# Z80UARTTEST.net
KiCad netlist of a schematic drawn in EAGLE
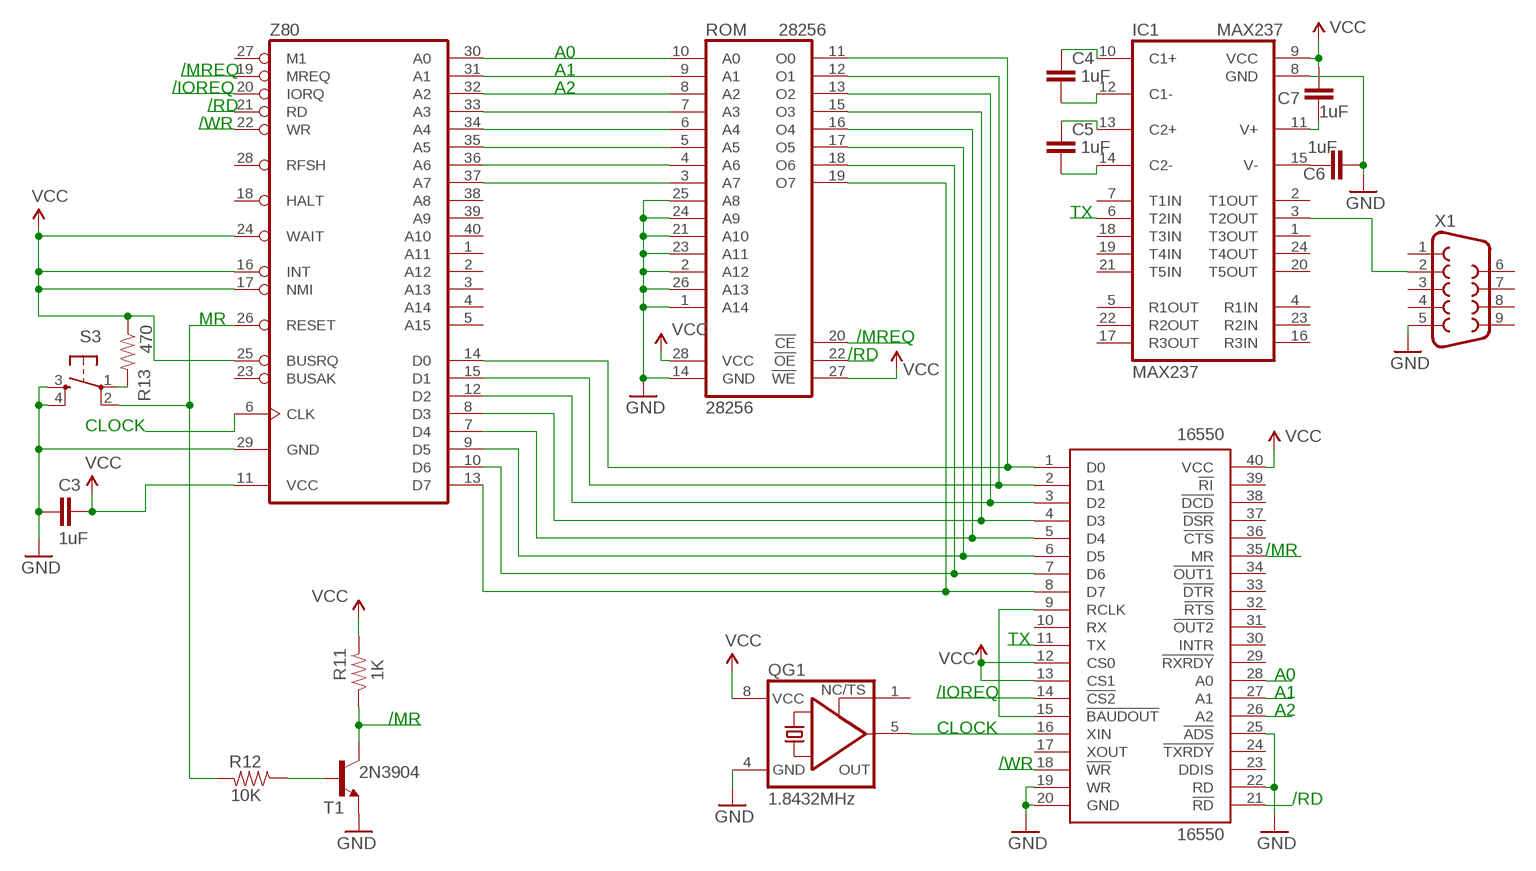
[diagram p0: schematic, sheet 1]

(export (version "E")
  (design (tool "Eeschema 10.0.6"))
  (components
    (comp (ref "C3")
      (value "1uF")
      (footprint "eagle-import:E5-5")
      (libsource (lib "eagle-import") (part "CAP"))
    )
    (comp (ref "C4")
      (value "1uF")
      (footprint "eagle-import:E5-5")
      (libsource (lib "eagle-import") (part "CAP"))
    )
    (comp (ref "C5")
      (value "1uF")
      (footprint "eagle-import:E5-5")
      (libsource (lib "eagle-import") (part "CAP"))
    )
    (comp (ref "C6")
      (value "1uF")
      (footprint "eagle-import:E5-5")
      (libsource (lib "eagle-import") (part "CAP"))
    )
    (comp (ref "C7")
      (value "1uF")
      (footprint "eagle-import:E5-5")
      (libsource (lib "eagle-import") (part "CAP"))
    )
    (comp (ref "IC1")
      (value "MAX237")
      (footprint "eagle-import:DIL24-3")
      (fields (field (name "MPN") "MAX237CNG+"))
      (libsource (lib "eagle-import") (part "MAX237"))
    )
    (comp (ref "QG1")
      (value "1.8432MHz")
      (footprint "eagle-import:DIL08S")
      (libsource (lib "eagle-import") (part "XO-8"))
    )
    (comp (ref "R11")
      (value "1K")
      (footprint "eagle-import:AXIAL-0.4")
      (libsource (lib "eagle-import") (part "RESISTORPTH-1/4W"))
    )
    (comp (ref "R12")
      (value "10K")
      (footprint "eagle-import:AXIAL-0.4")
      (libsource (lib "eagle-import") (part "RESISTORPTH-1/4W"))
    )
    (comp (ref "R13")
      (value "470")
      (footprint "eagle-import:AXIAL-0.4")
      (libsource (lib "eagle-import") (part "RESISTORPTH-1/4W"))
    )
    (comp (ref "ROM")
      (value "28256")
      (footprint "eagle-import:DIL28")
      (libsource (lib "eagle-import") (part "28256"))
    )
    (comp (ref "S3")
      (value "TAC_SWITCHPTH")
      (footprint "eagle-import:TACTILE-PTH")
      (libsource (lib "eagle-import") (part "TAC_SWITCHPTH"))
    )
    (comp (ref "T1")
      (value "2N3904")
      (footprint "eagle-import:TO92")
      (libsource (lib "eagle-import") (part "2N3904"))
    )
    (comp (ref "U$1")
      (value "16550")
      (footprint "eagle-import:DIL40")
      (libsource (lib "eagle-import") (part "16550"))
    )
    (comp (ref "X1")
      (value "DB9FEMALE")
      (footprint "eagle-import:DB9")
      (libsource (lib "eagle-import") (part "DB9FEMALE"))
    )
    (comp (ref "Z80")
      (value "Z80CPU")
      (footprint "eagle-import:DIL40")
      (libsource (lib "eagle-import") (part "Z80CPU"))
    )
  )
  (nets
    (net (code "1") (name "/A0") (class "Default")
      (node (ref "ROM") (pin "10") (pinfunction "A0_10") (pintype "input"))
      (node (ref "U$1") (pin "28") (pinfunction "A0_28") (pintype "bidirectional"))
      (node (ref "Z80") (pin "30") (pinfunction "A0_30") (pintype "output"))
    )
    (net (code "2") (name "/A1") (class "Default")
      (node (ref "ROM") (pin "9") (pinfunction "A1_9") (pintype "input"))
      (node (ref "U$1") (pin "27") (pinfunction "A1_27") (pintype "bidirectional"))
      (node (ref "Z80") (pin "31") (pinfunction "A1_31") (pintype "output"))
    )
    (net (code "3") (name "/A2") (class "Default")
      (node (ref "ROM") (pin "8") (pinfunction "A2_8") (pintype "input"))
      (node (ref "U$1") (pin "26") (pinfunction "A2_26") (pintype "bidirectional"))
      (node (ref "Z80") (pin "32") (pinfunction "A2_32") (pintype "output"))
    )
    (net (code "4") (name "/CLOCK") (class "Default")
      (node (ref "QG1") (pin "5") (pinfunction "OUT_5") (pintype "output"))
      (node (ref "U$1") (pin "16") (pinfunction "XIN_16") (pintype "bidirectional"))
      (node (ref "Z80") (pin "6") (pinfunction "CLK_6") (pintype "input"))
    )
    (net (code "5") (name "/TX") (class "Default")
      (node (ref "IC1") (pin "6") (pinfunction "T2IN_6") (pintype "input"))
      (node (ref "U$1") (pin "11") (pinfunction "TX_11") (pintype "bidirectional"))
    )
    (net (code "6") (name "/{slash}IOREQ") (class "Default")
      (node (ref "U$1") (pin "14") (pinfunction "~{CS2}_14") (pintype "bidirectional"))
      (node (ref "Z80") (pin "20") (pinfunction "IORQ_20") (pintype "output"))
    )
    (net (code "7") (name "/{slash}MR") (class "Default")
      (node (ref "R11") (pin "P$1") (pinfunction "1_P$1") (pintype "passive"))
      (node (ref "T1") (pin "1") (pinfunction "C_1") (pintype "passive"))
      (node (ref "U$1") (pin "35") (pinfunction "MR_35") (pintype "bidirectional"))
    )
    (net (code "8") (name "/{slash}MREQ") (class "Default")
      (node (ref "ROM") (pin "20") (pinfunction "~{CE}_20") (pintype "input"))
      (node (ref "Z80") (pin "19") (pinfunction "MREQ_19") (pintype "output"))
    )
    (net (code "9") (name "/{slash}RD") (class "Default")
      (node (ref "ROM") (pin "22") (pinfunction "~{OE}_22") (pintype "input"))
      (node (ref "U$1") (pin "21") (pinfunction "~{RD}_21") (pintype "bidirectional"))
      (node (ref "Z80") (pin "21") (pinfunction "RD_21") (pintype "output"))
    )
    (net (code "10") (name "/{slash}WR") (class "Default")
      (node (ref "U$1") (pin "18") (pinfunction "~{WR}_18") (pintype "bidirectional"))
      (node (ref "Z80") (pin "22") (pinfunction "WR_22") (pintype "output"))
    )
    (net (code "11") (name "GND") (class "Default")
      (node (ref "C3") (pin "-") (pinfunction "2_-") (pintype "passive"))
      (node (ref "C6") (pin "+") (pinfunction "1_+") (pintype "passive"))
      (node (ref "IC1") (pin "8") (pinfunction "GND_8") (pintype "bidirectional"))
      (node (ref "QG1") (pin "4") (pinfunction "GND_4") (pintype "power_in"))
      (node (ref "ROM") (pin "1") (pinfunction "A14_1") (pintype "input"))
      (node (ref "ROM") (pin "14") (pinfunction "GND_14") (pintype "tri_state"))
      (node (ref "ROM") (pin "2") (pinfunction "A12_2") (pintype "input"))
      (node (ref "ROM") (pin "21") (pinfunction "A10_21") (pintype "input"))
      (node (ref "ROM") (pin "23") (pinfunction "A11_23") (pintype "input"))
      (node (ref "ROM") (pin "24") (pinfunction "A9_24") (pintype "input"))
      (node (ref "ROM") (pin "25") (pinfunction "A8_25") (pintype "input"))
      (node (ref "ROM") (pin "26") (pinfunction "A13_26") (pintype "input"))
      (node (ref "S3") (pin "3") (pinfunction "3_3") (pintype "passive"))
      (node (ref "S3") (pin "4") (pinfunction "4_4") (pintype "passive"))
      (node (ref "T1") (pin "3") (pinfunction "E_3") (pintype "passive"))
      (node (ref "U$1") (pin "19") (pinfunction "WR_19") (pintype "bidirectional"))
      (node (ref "U$1") (pin "20") (pinfunction "GND_20") (pintype "bidirectional"))
      (node (ref "U$1") (pin "22") (pinfunction "RD_22") (pintype "bidirectional"))
      (node (ref "U$1") (pin "25") (pinfunction "~{ADS}_25") (pintype "bidirectional"))
      (node (ref "X1") (pin "5") (pinfunction "5_5") (pintype "passive"))
      (node (ref "Z80") (pin "29") (pinfunction "GND_29") (pintype "power_in"))
    )
    (net (code "12") (name "Net-(C4-1)") (class "Default")
      (node (ref "C4") (pin "+") (pinfunction "1_+") (pintype "passive"))
      (node (ref "IC1") (pin "10") (pinfunction "C1+_10") (pintype "bidirectional"))
    )
    (net (code "13") (name "Net-(C4-2)") (class "Default")
      (node (ref "C4") (pin "-") (pinfunction "2_-") (pintype "passive"))
      (node (ref "IC1") (pin "12") (pinfunction "C1-_12") (pintype "bidirectional"))
    )
    (net (code "14") (name "Net-(C5-1)") (class "Default")
      (node (ref "C5") (pin "+") (pinfunction "1_+") (pintype "passive"))
      (node (ref "IC1") (pin "13") (pinfunction "C2+_13") (pintype "bidirectional"))
    )
    (net (code "15") (name "Net-(C5-2)") (class "Default")
      (node (ref "C5") (pin "-") (pinfunction "2_-") (pintype "passive"))
      (node (ref "IC1") (pin "14") (pinfunction "C2-_14") (pintype "bidirectional"))
    )
    (net (code "16") (name "Net-(C6-2)") (class "Default")
      (node (ref "C6") (pin "-") (pinfunction "2_-") (pintype "passive"))
      (node (ref "IC1") (pin "15") (pinfunction "V-_15") (pintype "bidirectional"))
    )
    (net (code "17") (name "Net-(C7-1)") (class "Default")
      (node (ref "C7") (pin "+") (pinfunction "1_+") (pintype "passive"))
      (node (ref "IC1") (pin "11") (pinfunction "V+_11") (pintype "bidirectional"))
    )
    (net (code "18") (name "Net-(IC1-T2OUT)") (class "Default")
      (node (ref "IC1") (pin "3") (pinfunction "T2OUT_3") (pintype "output"))
      (node (ref "X1") (pin "2") (pinfunction "2_2") (pintype "passive"))
    )
    (net (code "19") (name "Net-(R12-1)") (class "Default")
      (node (ref "R12") (pin "P$1") (pinfunction "1_P$1") (pintype "passive"))
      (node (ref "T1") (pin "2") (pinfunction "B_2") (pintype "passive"))
    )
    (net (code "20") (name "Net-(R12-2)") (class "Default")
      (node (ref "R12") (pin "P$2") (pinfunction "2_P$2") (pintype "passive"))
      (node (ref "S3") (pin "2") (pinfunction "2_2") (pintype "passive"))
      (node (ref "Z80") (pin "26") (pinfunction "RESET_26") (pintype "input"))
    )
    (net (code "21") (name "Net-(R13-2)") (class "Default")
      (node (ref "R13") (pin "P$2") (pinfunction "2_P$2") (pintype "passive"))
      (node (ref "S3") (pin "1") (pinfunction "1_1") (pintype "passive"))
    )
    (net (code "22") (name "Net-(ROM-A3)") (class "Default")
      (node (ref "ROM") (pin "7") (pinfunction "A3_7") (pintype "input"))
      (node (ref "Z80") (pin "33") (pinfunction "A3_33") (pintype "output"))
    )
    (net (code "23") (name "Net-(ROM-A4)") (class "Default")
      (node (ref "ROM") (pin "6") (pinfunction "A4_6") (pintype "input"))
      (node (ref "Z80") (pin "34") (pinfunction "A4_34") (pintype "output"))
    )
    (net (code "24") (name "Net-(ROM-A5)") (class "Default")
      (node (ref "ROM") (pin "5") (pinfunction "A5_5") (pintype "input"))
      (node (ref "Z80") (pin "35") (pinfunction "A5_35") (pintype "output"))
    )
    (net (code "25") (name "Net-(ROM-A6)") (class "Default")
      (node (ref "ROM") (pin "4") (pinfunction "A6_4") (pintype "input"))
      (node (ref "Z80") (pin "36") (pinfunction "A6_36") (pintype "output"))
    )
    (net (code "26") (name "Net-(ROM-A7)") (class "Default")
      (node (ref "ROM") (pin "3") (pinfunction "A7_3") (pintype "input"))
      (node (ref "Z80") (pin "37") (pinfunction "A7_37") (pintype "output"))
    )
    (net (code "27") (name "Net-(ROM-O0)") (class "Default")
      (node (ref "ROM") (pin "11") (pinfunction "O0_11") (pintype "tri_state"))
      (node (ref "U$1") (pin "1") (pinfunction "D0_1") (pintype "bidirectional"))
      (node (ref "Z80") (pin "14") (pinfunction "D0_14") (pintype "bidirectional"))
    )
    (net (code "28") (name "Net-(ROM-O1)") (class "Default")
      (node (ref "ROM") (pin "12") (pinfunction "O1_12") (pintype "tri_state"))
      (node (ref "U$1") (pin "2") (pinfunction "D1_2") (pintype "bidirectional"))
      (node (ref "Z80") (pin "15") (pinfunction "D1_15") (pintype "bidirectional"))
    )
    (net (code "29") (name "Net-(ROM-O2)") (class "Default")
      (node (ref "ROM") (pin "13") (pinfunction "O2_13") (pintype "tri_state"))
      (node (ref "U$1") (pin "3") (pinfunction "D2_3") (pintype "bidirectional"))
      (node (ref "Z80") (pin "12") (pinfunction "D2_12") (pintype "bidirectional"))
    )
    (net (code "30") (name "Net-(ROM-O3)") (class "Default")
      (node (ref "ROM") (pin "15") (pinfunction "O3_15") (pintype "tri_state"))
      (node (ref "U$1") (pin "4") (pinfunction "D3_4") (pintype "bidirectional"))
      (node (ref "Z80") (pin "8") (pinfunction "D3_8") (pintype "bidirectional"))
    )
    (net (code "31") (name "Net-(ROM-O4)") (class "Default")
      (node (ref "ROM") (pin "16") (pinfunction "O4_16") (pintype "tri_state"))
      (node (ref "U$1") (pin "5") (pinfunction "D4_5") (pintype "bidirectional"))
      (node (ref "Z80") (pin "7") (pinfunction "D4_7") (pintype "bidirectional"))
    )
    (net (code "32") (name "Net-(ROM-O5)") (class "Default")
      (node (ref "ROM") (pin "17") (pinfunction "O5_17") (pintype "tri_state"))
      (node (ref "U$1") (pin "6") (pinfunction "D5_6") (pintype "bidirectional"))
      (node (ref "Z80") (pin "9") (pinfunction "D5_9") (pintype "bidirectional"))
    )
    (net (code "33") (name "Net-(ROM-O6)") (class "Default")
      (node (ref "ROM") (pin "18") (pinfunction "O6_18") (pintype "tri_state"))
      (node (ref "U$1") (pin "7") (pinfunction "D6_7") (pintype "bidirectional"))
      (node (ref "Z80") (pin "10") (pinfunction "D6_10") (pintype "bidirectional"))
    )
    (net (code "34") (name "Net-(ROM-O7)") (class "Default")
      (node (ref "ROM") (pin "19") (pinfunction "O7_19") (pintype "tri_state"))
      (node (ref "U$1") (pin "8") (pinfunction "D7_8") (pintype "bidirectional"))
      (node (ref "Z80") (pin "13") (pinfunction "D7_13") (pintype "bidirectional"))
    )
    (net (code "35") (name "Net-(U$1-RCLK)") (class "Default")
      (node (ref "U$1") (pin "15") (pinfunction "~{BAUDOUT}_15") (pintype "bidirectional"))
      (node (ref "U$1") (pin "9") (pinfunction "RCLK_9") (pintype "bidirectional"))
    )
    (net (code "36") (name "VCC") (class "Default")
      (node (ref "C3") (pin "+") (pinfunction "1_+") (pintype "passive"))
      (node (ref "C7") (pin "-") (pinfunction "2_-") (pintype "passive"))
      (node (ref "IC1") (pin "9") (pinfunction "VCC_9") (pintype "bidirectional"))
      (node (ref "QG1") (pin "8") (pinfunction "VCC_8") (pintype "power_in"))
      (node (ref "R11") (pin "P$2") (pinfunction "2_P$2") (pintype "passive"))
      (node (ref "R13") (pin "P$1") (pinfunction "1_P$1") (pintype "passive"))
      (node (ref "ROM") (pin "27") (pinfunction "~{WE}_27") (pintype "input"))
      (node (ref "ROM") (pin "28") (pinfunction "VCC_28") (pintype "tri_state"))
      (node (ref "U$1") (pin "12") (pinfunction "CS0_12") (pintype "bidirectional"))
      (node (ref "U$1") (pin "13") (pinfunction "CS1_13") (pintype "bidirectional"))
      (node (ref "U$1") (pin "40") (pinfunction "VCC_40") (pintype "bidirectional"))
      (node (ref "Z80") (pin "11") (pinfunction "VCC_11") (pintype "power_in"))
      (node (ref "Z80") (pin "16") (pinfunction "INT_16") (pintype "input"))
      (node (ref "Z80") (pin "17") (pinfunction "NMI_17") (pintype "input"))
      (node (ref "Z80") (pin "24") (pinfunction "WAIT_24") (pintype "input"))
      (node (ref "Z80") (pin "25") (pinfunction "BUSRQ_25") (pintype "input"))
    )
    (net (code "37") (name "unconnected-(IC1-R1IN-Pad4)") (class "Default")
      (node (ref "IC1") (pin "4") (pinfunction "R1IN_4") (pintype "input"))
    )
    (net (code "38") (name "unconnected-(IC1-R1OUT-Pad5)") (class "Default")
      (node (ref "IC1") (pin "5") (pinfunction "R1OUT_5") (pintype "output"))
    )
    (net (code "39") (name "unconnected-(IC1-R2IN-Pad23)") (class "Default")
      (node (ref "IC1") (pin "23") (pinfunction "R2IN_23") (pintype "input"))
    )
    (net (code "40") (name "unconnected-(IC1-R2OUT-Pad22)") (class "Default")
      (node (ref "IC1") (pin "22") (pinfunction "R2OUT_22") (pintype "output"))
    )
    (net (code "41") (name "unconnected-(IC1-R3IN-Pad16)") (class "Default")
      (node (ref "IC1") (pin "16") (pinfunction "R3IN_16") (pintype "input"))
    )
    (net (code "42") (name "unconnected-(IC1-R3OUT-Pad17)") (class "Default")
      (node (ref "IC1") (pin "17") (pinfunction "R3OUT_17") (pintype "output"))
    )
    (net (code "43") (name "unconnected-(IC1-T1IN-Pad7)") (class "Default")
      (node (ref "IC1") (pin "7") (pinfunction "T1IN_7") (pintype "input"))
    )
    (net (code "44") (name "unconnected-(IC1-T1OUT-Pad2)") (class "Default")
      (node (ref "IC1") (pin "2") (pinfunction "T1OUT_2") (pintype "output"))
    )
    (net (code "45") (name "unconnected-(IC1-T3IN-Pad18)") (class "Default")
      (node (ref "IC1") (pin "18") (pinfunction "T3IN_18") (pintype "input"))
    )
    (net (code "46") (name "unconnected-(IC1-T3OUT-Pad1)") (class "Default")
      (node (ref "IC1") (pin "1") (pinfunction "T3OUT_1") (pintype "output"))
    )
    (net (code "47") (name "unconnected-(IC1-T4IN-Pad19)") (class "Default")
      (node (ref "IC1") (pin "19") (pinfunction "T4IN_19") (pintype "input"))
    )
    (net (code "48") (name "unconnected-(IC1-T4OUT-Pad24)") (class "Default")
      (node (ref "IC1") (pin "24") (pinfunction "T4OUT_24") (pintype "output"))
    )
    (net (code "49") (name "unconnected-(IC1-T5IN-Pad21)") (class "Default")
      (node (ref "IC1") (pin "21") (pinfunction "T5IN_21") (pintype "input"))
    )
    (net (code "50") (name "unconnected-(IC1-T5OUT-Pad20)") (class "Default")
      (node (ref "IC1") (pin "20") (pinfunction "T5OUT_20") (pintype "output"))
    )
    (net (code "51") (name "unconnected-(QG1-TS-Pad1)") (class "Default")
      (node (ref "QG1") (pin "1") (pinfunction "TS_1") (pintype "passive"))
    )
    (net (code "52") (name "unconnected-(U$1-DDIS-Pad23)") (class "Default")
      (node (ref "U$1") (pin "23") (pinfunction "DDIS_23") (pintype "bidirectional"))
    )
    (net (code "53") (name "unconnected-(U$1-INTR-Pad30)") (class "Default")
      (node (ref "U$1") (pin "30") (pinfunction "INTR_30") (pintype "bidirectional"))
    )
    (net (code "54") (name "unconnected-(U$1-RX-Pad10)") (class "Default")
      (node (ref "U$1") (pin "10") (pinfunction "RX_10") (pintype "bidirectional"))
    )
    (net (code "55") (name "unconnected-(U$1-XOUT-Pad17)") (class "Default")
      (node (ref "U$1") (pin "17") (pinfunction "XOUT_17") (pintype "bidirectional"))
    )
    (net (code "56") (name "unconnected-(U$1-~{CTS}-Pad36)") (class "Default")
      (node (ref "U$1") (pin "36") (pinfunction "~{CTS}_36") (pintype "bidirectional"))
    )
    (net (code "57") (name "unconnected-(U$1-~{DCD}-Pad38)") (class "Default")
      (node (ref "U$1") (pin "38") (pinfunction "~{DCD}_38") (pintype "bidirectional"))
    )
    (net (code "58") (name "unconnected-(U$1-~{DSR}-Pad37)") (class "Default")
      (node (ref "U$1") (pin "37") (pinfunction "~{DSR}_37") (pintype "bidirectional"))
    )
    (net (code "59") (name "unconnected-(U$1-~{DTR}-Pad33)") (class "Default")
      (node (ref "U$1") (pin "33") (pinfunction "~{DTR}_33") (pintype "bidirectional"))
    )
    (net (code "60") (name "unconnected-(U$1-~{OUT1}-Pad34)") (class "Default")
      (node (ref "U$1") (pin "34") (pinfunction "~{OUT1}_34") (pintype "bidirectional"))
    )
    (net (code "61") (name "unconnected-(U$1-~{OUT2}-Pad31)") (class "Default")
      (node (ref "U$1") (pin "31") (pinfunction "~{OUT2}_31") (pintype "bidirectional"))
    )
    (net (code "62") (name "unconnected-(U$1-~{RI}-Pad39)") (class "Default")
      (node (ref "U$1") (pin "39") (pinfunction "~{RI}_39") (pintype "bidirectional"))
    )
    (net (code "63") (name "unconnected-(U$1-~{RTS}-Pad32)") (class "Default")
      (node (ref "U$1") (pin "32") (pinfunction "~{RTS}_32") (pintype "bidirectional"))
    )
    (net (code "64") (name "unconnected-(U$1-~{RXRDY}-Pad29)") (class "Default")
      (node (ref "U$1") (pin "29") (pinfunction "~{RXRDY}_29") (pintype "bidirectional"))
    )
    (net (code "65") (name "unconnected-(U$1-~{TXRDY}-Pad24)") (class "Default")
      (node (ref "U$1") (pin "24") (pinfunction "~{TXRDY}_24") (pintype "bidirectional"))
    )
    (net (code "66") (name "unconnected-(X1-Pad1)") (class "Default")
      (node (ref "X1") (pin "1") (pinfunction "1_1") (pintype "passive"))
    )
    (net (code "67") (name "unconnected-(X1-Pad3)") (class "Default")
      (node (ref "X1") (pin "3") (pinfunction "3_3") (pintype "passive"))
    )
    (net (code "68") (name "unconnected-(X1-Pad4)") (class "Default")
      (node (ref "X1") (pin "4") (pinfunction "4_4") (pintype "passive"))
    )
    (net (code "69") (name "unconnected-(X1-Pad6)") (class "Default")
      (node (ref "X1") (pin "6") (pinfunction "6_6") (pintype "passive"))
    )
    (net (code "70") (name "unconnected-(X1-Pad7)") (class "Default")
      (node (ref "X1") (pin "7") (pinfunction "7_7") (pintype "passive"))
    )
    (net (code "71") (name "unconnected-(X1-Pad8)") (class "Default")
      (node (ref "X1") (pin "8") (pinfunction "8_8") (pintype "passive"))
    )
    (net (code "72") (name "unconnected-(X1-Pad9)") (class "Default")
      (node (ref "X1") (pin "9") (pinfunction "9_9") (pintype "passive"))
    )
    (net (code "73") (name "unconnected-(Z80-A8-Pad38)") (class "Default")
      (node (ref "Z80") (pin "38") (pinfunction "A8_38") (pintype "output"))
    )
    (net (code "74") (name "unconnected-(Z80-A9-Pad39)") (class "Default")
      (node (ref "Z80") (pin "39") (pinfunction "A9_39") (pintype "output"))
    )
    (net (code "75") (name "unconnected-(Z80-A10-Pad40)") (class "Default")
      (node (ref "Z80") (pin "40") (pinfunction "A10_40") (pintype "output"))
    )
    (net (code "76") (name "unconnected-(Z80-A11-Pad1)") (class "Default")
      (node (ref "Z80") (pin "1") (pinfunction "A11_1") (pintype "output"))
    )
    (net (code "77") (name "unconnected-(Z80-A12-Pad2)") (class "Default")
      (node (ref "Z80") (pin "2") (pinfunction "A12_2") (pintype "output"))
    )
    (net (code "78") (name "unconnected-(Z80-A13-Pad3)") (class "Default")
      (node (ref "Z80") (pin "3") (pinfunction "A13_3") (pintype "output"))
    )
    (net (code "79") (name "unconnected-(Z80-A14-Pad4)") (class "Default")
      (node (ref "Z80") (pin "4") (pinfunction "A14_4") (pintype "output"))
    )
    (net (code "80") (name "unconnected-(Z80-A15-Pad5)") (class "Default")
      (node (ref "Z80") (pin "5") (pinfunction "A15_5") (pintype "output"))
    )
    (net (code "81") (name "unconnected-(Z80-BUSAK-Pad23)") (class "Default")
      (node (ref "Z80") (pin "23") (pinfunction "BUSAK_23") (pintype "output"))
    )
    (net (code "82") (name "unconnected-(Z80-HALT-Pad18)") (class "Default")
      (node (ref "Z80") (pin "18") (pinfunction "HALT_18") (pintype "output"))
    )
    (net (code "83") (name "unconnected-(Z80-M1-Pad27)") (class "Default")
      (node (ref "Z80") (pin "27") (pinfunction "M1_27") (pintype "output"))
    )
    (net (code "84") (name "unconnected-(Z80-RFSH-Pad28)") (class "Default")
      (node (ref "Z80") (pin "28") (pinfunction "RFSH_28") (pintype "output"))
    )
  )
)
